# Eggs_Control.net
KiCad netlist of a schematic drawn in EAGLE
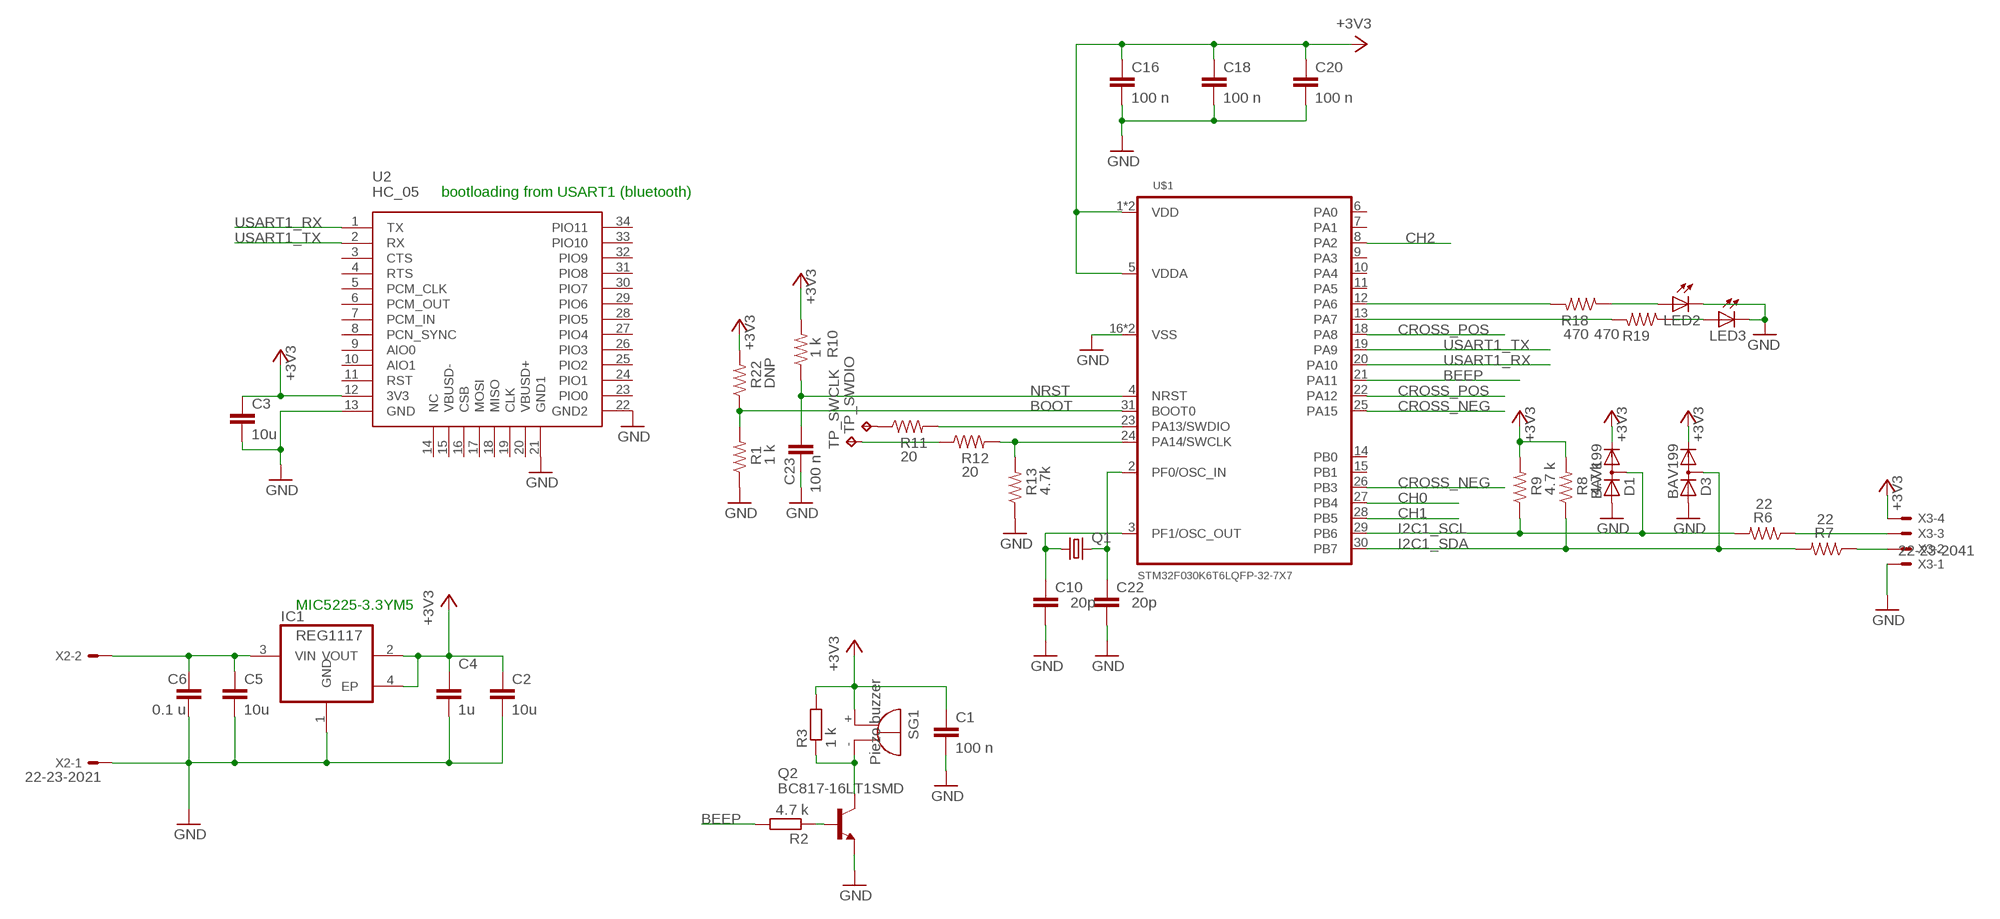
[diagram p0: schematic, sheet 1]
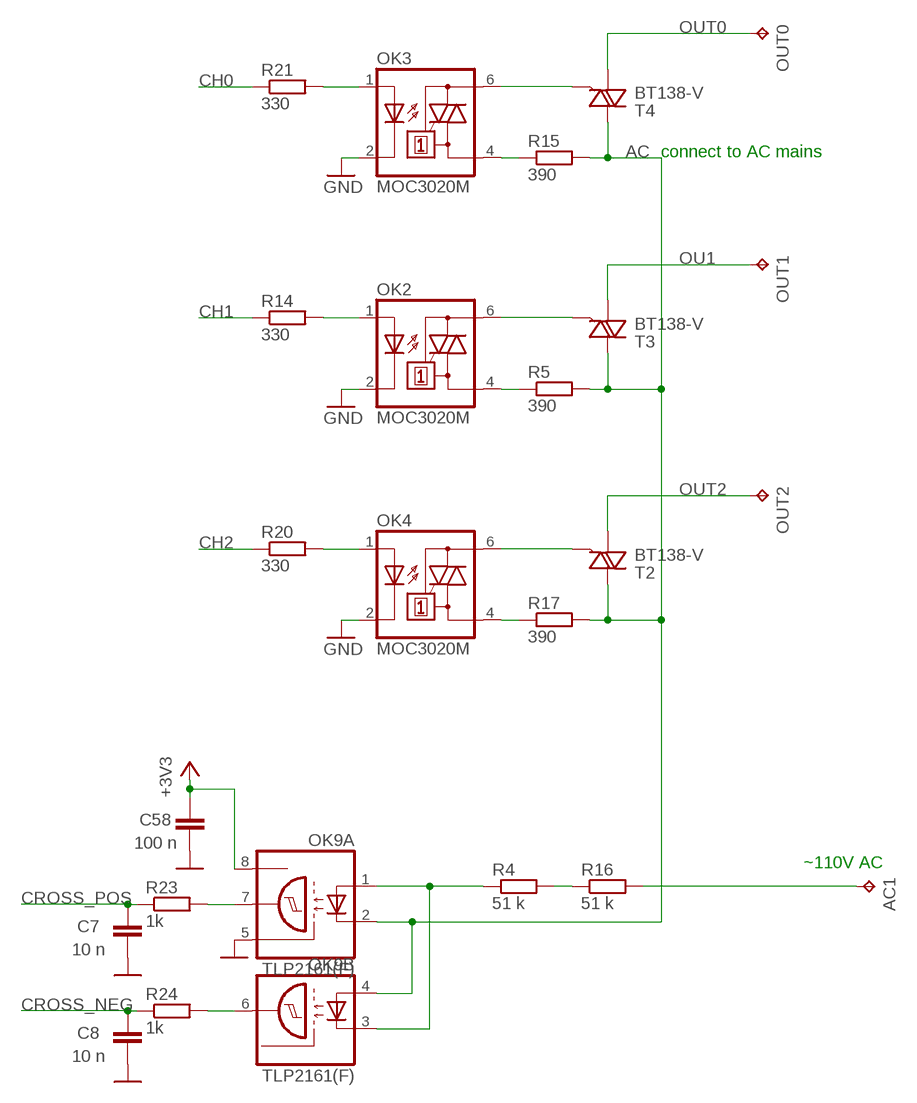
[diagram p1: schematic, sheet 2]

(export (version "E")
  (design (tool "Eeschema 10.0.6"))
  (components
    (comp (ref "C1")
      (value "100 n")
      (footprint "eagle-import:C0603")
      (libsource (lib "eagle-import") (part "C-EUC0603"))
    )
    (comp (ref "C2")
      (value "10u")
      (footprint "eagle-import:C0805")
      (libsource (lib "eagle-import") (part "C-EUC0805"))
    )
    (comp (ref "C3")
      (value "10u")
      (footprint "eagle-import:C0805")
      (libsource (lib "eagle-import") (part "C-EUC0805"))
    )
    (comp (ref "C4")
      (value "1u")
      (footprint "eagle-import:C0603")
      (libsource (lib "eagle-import") (part "C-EUC0603"))
    )
    (comp (ref "C5")
      (value "10u")
      (footprint "eagle-import:C0805")
      (libsource (lib "eagle-import") (part "C-EUC0805"))
    )
    (comp (ref "C6")
      (value "0.1 u")
      (footprint "eagle-import:C0603")
      (libsource (lib "eagle-import") (part "C-EUC0603"))
    )
    (comp (ref "C10")
      (value "20p")
      (footprint "eagle-import:C0603")
      (libsource (lib "eagle-import") (part "C-EUC0603"))
    )
    (comp (ref "C16")
      (value "100 n")
      (footprint "eagle-import:C0603")
      (libsource (lib "eagle-import") (part "C-EUC0603"))
    )
    (comp (ref "C18")
      (value "100 n")
      (footprint "eagle-import:C0603")
      (libsource (lib "eagle-import") (part "C-EUC0603"))
    )
    (comp (ref "C20")
      (value "100 n")
      (footprint "eagle-import:C0603")
      (libsource (lib "eagle-import") (part "C-EUC0603"))
    )
    (comp (ref "C22")
      (value "20p")
      (footprint "eagle-import:C0603")
      (libsource (lib "eagle-import") (part "C-EUC0603"))
    )
    (comp (ref "C23")
      (value "100 n")
      (footprint "eagle-import:C0603")
      (libsource (lib "eagle-import") (part "C-EUC0603"))
    )
    (comp (ref "D1")
      (value "BAV199")
      (footprint "eagle-import:SOT23")
      (libsource (lib "eagle-import") (part "BAV199"))
    )
    (comp (ref "D3")
      (value "BAV199")
      (footprint "eagle-import:SOT23")
      (libsource (lib "eagle-import") (part "BAV199"))
    )
    (comp (ref "IC1")
      (value "REG1117")
      (footprint "eagle-import:SOT223")
      (libsource (lib "eagle-import") (part "REG1117"))
    )
    (comp (ref "LED2")
      (value "LED_ESML0603")
      (footprint "eagle-import:LED_SML0603")
      (libsource (lib "eagle-import") (part "LED_ESML0603"))
    )
    (comp (ref "LED3")
      (value "LED_ESML0603")
      (footprint "eagle-import:LED_SML0603")
      (libsource (lib "eagle-import") (part "LED_ESML0603"))
    )
    (comp (ref "Q1")
      (value "CRYSTALSM49")
      (footprint "eagle-import:SM49")
      (libsource (lib "eagle-import") (part "CRYSTALSM49"))
    )
    (comp (ref "Q2")
      (value "BC817-16LT1SMD")
      (footprint "eagle-import:SOT23-BEC")
      (libsource (lib "eagle-import") (part "BC817SMD-16LT1"))
    )
    (comp (ref "R1")
      (value "1 k")
      (footprint "eagle-import:R0603")
      (libsource (lib "eagle-import") (part "R-US_R0603"))
    )
    (comp (ref "R2")
      (value "4.7 k")
      (footprint "eagle-import:R0603")
      (libsource (lib "eagle-import") (part "resistor_R-EU_R0603"))
    )
    (comp (ref "R3")
      (value "1 k")
      (footprint "eagle-import:R0603")
      (libsource (lib "eagle-import") (part "resistor_R-EU_R0603"))
    )
    (comp (ref "R6")
      (value "22")
      (footprint "eagle-import:R0603")
      (libsource (lib "eagle-import") (part "R-US_R0603"))
    )
    (comp (ref "R7")
      (value "22")
      (footprint "eagle-import:R0603")
      (libsource (lib "eagle-import") (part "R-US_R0603"))
    )
    (comp (ref "R8")
      (value "4.7 k")
      (footprint "eagle-import:R0603")
      (libsource (lib "eagle-import") (part "R-US_R0603"))
    )
    (comp (ref "R9")
      (value "4.7 k")
      (footprint "eagle-import:R0603")
      (libsource (lib "eagle-import") (part "R-US_R0603"))
    )
    (comp (ref "R10")
      (value "1 k")
      (footprint "eagle-import:R0603")
      (libsource (lib "eagle-import") (part "R-US_R0603"))
    )
    (comp (ref "R11")
      (value "20")
      (footprint "eagle-import:R0603")
      (libsource (lib "eagle-import") (part "R-US_R0603"))
    )
    (comp (ref "R12")
      (value "20")
      (footprint "eagle-import:R0603")
      (libsource (lib "eagle-import") (part "R-US_R0603"))
    )
    (comp (ref "R13")
      (value "4.7k")
      (footprint "eagle-import:R0603")
      (libsource (lib "eagle-import") (part "R-US_R0603"))
    )
    (comp (ref "R18")
      (value "470")
      (footprint "eagle-import:R0603")
      (libsource (lib "eagle-import") (part "R-US_R0603"))
    )
    (comp (ref "R19")
      (value "470")
      (footprint "eagle-import:R0603")
      (libsource (lib "eagle-import") (part "R-US_R0603"))
    )
    (comp (ref "R22")
      (value "DNP")
      (footprint "eagle-import:R0603")
      (libsource (lib "eagle-import") (part "R-US_R0603"))
    )
    (comp (ref "SG1")
      (value "Piezo buzzer")
      (footprint "eagle-import:F_HMB")
      (libsource (lib "eagle-import") (part "F/HMB"))
    )
    (comp (ref "TP_SWCLK")
      (value "TPTP10SQ")
      (footprint "eagle-import:TP10SQ")
      (libsource (lib "eagle-import") (part "TPTP10SQ"))
    )
    (comp (ref "TP_SWDIO")
      (value "TPTP10SQ")
      (footprint "eagle-import:TP10SQ")
      (libsource (lib "eagle-import") (part "TPTP10SQ"))
    )
    (comp (ref "U$1")
      (value "STM32F030K6T6LQFP-32-7X7")
      (footprint "eagle-import:LQFP32-7X7")
      (libsource (lib "eagle-import") (part "STM32F030K6T6LQFP-32-7X7"))
    )
    (comp (ref "U2")
      (value "HC_05")
      (footprint "eagle-import:BLUETOOTH_SMD")
      (libsource (lib "eagle-import") (part "HC_05"))
    )
    (comp (ref "X2")
      (value "22-23-2021")
      (footprint "eagle-import:22-23-2021")
      (fields (field (name "MF") "MOLEX"))
      (libsource (lib "eagle-import") (part "22-23-2021"))
    )
    (comp (ref "X3")
      (value "22-23-2041")
      (footprint "eagle-import:22-23-2041")
      (fields (field (name "MF") "MOLEX"))
      (libsource (lib "eagle-import") (part "22-23-2041"))
    )
    (comp (ref "AC1")
      (value "TPPAD1-17")
      (footprint "eagle-import:P1-17")
      (libsource (lib "eagle-import") (part "TPPAD1-17"))
    )
    (comp (ref "C7")
      (value "10 n")
      (footprint "eagle-import:C0603")
      (libsource (lib "eagle-import") (part "C-EUC0603"))
    )
    (comp (ref "C8")
      (value "10 n")
      (footprint "eagle-import:C0603")
      (libsource (lib "eagle-import") (part "C-EUC0603"))
    )
    (comp (ref "C58")
      (value "100 n")
      (footprint "eagle-import:C0603")
      (libsource (lib "eagle-import") (part "C-EUC0603"))
    )
    (comp (ref "OK2")
      (value "MOC3020M")
      (footprint "eagle-import:DIL06")
      (fields (field (name "MF") "FAIRCHILD SEMICONDUCTOR") (field (name "MPN") "MOC3020-M"))
      (libsource (lib "eagle-import") (part "MOC30M20"))
    )
    (comp (ref "OK3")
      (value "MOC3020M")
      (footprint "eagle-import:DIL06")
      (fields (field (name "MF") "FAIRCHILD SEMICONDUCTOR") (field (name "MPN") "MOC3020-M"))
      (libsource (lib "eagle-import") (part "MOC30M20"))
    )
    (comp (ref "OK4")
      (value "MOC3020M")
      (footprint "eagle-import:DIL06")
      (fields (field (name "MF") "FAIRCHILD SEMICONDUCTOR") (field (name "MPN") "MOC3020-M"))
      (libsource (lib "eagle-import") (part "MOC30M20"))
    )
    (comp (ref "OK9")
      (value "TLP2161(F)")
      (footprint "eagle-import:SOIC08-FAIRCHILD")
      (libsource (lib "eagle-import") (part "TLP2161(F)"))
    )
    (comp (ref "OUT0")
      (value "TPPAD1-17")
      (footprint "eagle-import:P1-17")
      (libsource (lib "eagle-import") (part "TPPAD1-17"))
    )
    (comp (ref "OUT1")
      (value "TPPAD1-17")
      (footprint "eagle-import:P1-17")
      (libsource (lib "eagle-import") (part "TPPAD1-17"))
    )
    (comp (ref "OUT2")
      (value "TPPAD1-17")
      (footprint "eagle-import:P1-17")
      (libsource (lib "eagle-import") (part "TPPAD1-17"))
    )
    (comp (ref "R4")
      (value "51 k")
      (footprint "eagle-import:R1206")
      (libsource (lib "eagle-import") (part "resistor_R-EU_R1206"))
    )
    (comp (ref "R5")
      (value "390")
      (footprint "eagle-import:R0603")
      (libsource (lib "eagle-import") (part "R-EU_R0603"))
    )
    (comp (ref "R14")
      (value "330")
      (footprint "eagle-import:R0603")
      (libsource (lib "eagle-import") (part "R-EU_R0603"))
    )
    (comp (ref "R15")
      (value "390")
      (footprint "eagle-import:R0603")
      (libsource (lib "eagle-import") (part "R-EU_R0603"))
    )
    (comp (ref "R16")
      (value "51 k")
      (footprint "eagle-import:R1206")
      (libsource (lib "eagle-import") (part "resistor_R-EU_R1206"))
    )
    (comp (ref "R17")
      (value "390")
      (footprint "eagle-import:R0603")
      (libsource (lib "eagle-import") (part "R-EU_R0603"))
    )
    (comp (ref "R20")
      (value "330")
      (footprint "eagle-import:R0603")
      (libsource (lib "eagle-import") (part "R-EU_R0603"))
    )
    (comp (ref "R21")
      (value "330")
      (footprint "eagle-import:R0603")
      (libsource (lib "eagle-import") (part "R-EU_R0603"))
    )
    (comp (ref "R23")
      (value "1k")
      (footprint "eagle-import:R0603")
      (libsource (lib "eagle-import") (part "R-EU_R0603"))
    )
    (comp (ref "R24")
      (value "1k")
      (footprint "eagle-import:R0603")
      (libsource (lib "eagle-import") (part "R-EU_R0603"))
    )
    (comp (ref "T2")
      (value "BT138-V")
      (footprint "eagle-import:TO220BV")
      (libsource (lib "eagle-import") (part "BT138-V"))
    )
    (comp (ref "T3")
      (value "BT138-V")
      (footprint "eagle-import:TO220BV")
      (libsource (lib "eagle-import") (part "BT138-V"))
    )
    (comp (ref "T4")
      (value "BT138-V")
      (footprint "eagle-import:TO220BV")
      (libsource (lib "eagle-import") (part "BT138-V"))
    )
  )
  (nets
    (net (code "1") (name "+3V3") (class "Default")
      (node (ref "C1") (pin "1") (pinfunction "1_1") (pintype "passive"))
      (node (ref "C16") (pin "1") (pinfunction "1_1") (pintype "passive"))
      (node (ref "C18") (pin "1") (pinfunction "1_1") (pintype "passive"))
      (node (ref "C2") (pin "1") (pinfunction "1_1") (pintype "passive"))
      (node (ref "C20") (pin "1") (pinfunction "1_1") (pintype "passive"))
      (node (ref "C3") (pin "1") (pinfunction "1_1") (pintype "passive"))
      (node (ref "C4") (pin "1") (pinfunction "1_1") (pintype "passive"))
      (node (ref "C58") (pin "1") (pinfunction "1_1") (pintype "passive"))
      (node (ref "D1") (pin "2") (pinfunction "C_2") (pintype "passive"))
      (node (ref "D3") (pin "2") (pinfunction "C_2") (pintype "passive"))
      (node (ref "IC1") (pin "2") (pinfunction "VOUT_2") (pintype "output"))
      (node (ref "IC1") (pin "4") (pinfunction "EP_4") (pintype "output"))
      (node (ref "OK9") (pin "8") (pinfunction "VCC_8") (pintype "passive"))
      (node (ref "R10") (pin "2") (pinfunction "2_2") (pintype "passive"))
      (node (ref "R22") (pin "2") (pinfunction "2_2") (pintype "passive"))
      (node (ref "R3") (pin "2") (pinfunction "2_2") (pintype "passive"))
      (node (ref "R8") (pin "2") (pinfunction "2_2") (pintype "passive"))
      (node (ref "R9") (pin "2") (pinfunction "2_2") (pintype "passive"))
      (node (ref "SG1") (pin "+") (pinfunction "+_+") (pintype "passive"))
      (node (ref "U$1") (pin "1") (pinfunction "VDD_1") (pintype "bidirectional"))
      (node (ref "U$1") (pin "17") (pinfunction "VDD_17") (pintype "bidirectional"))
      (node (ref "U$1") (pin "5") (pinfunction "VDDA_5") (pintype "bidirectional"))
      (node (ref "U2") (pin "12") (pinfunction "3V3_12") (pintype "bidirectional"))
      (node (ref "X3") (pin "4") (pinfunction "S_4") (pintype "passive"))
    )
    (net (code "2") (name "AC") (class "Default")
      (node (ref "OK9") (pin "2") (pinfunction "C_2") (pintype "passive"))
      (node (ref "OK9") (pin "4") (pinfunction "A_4") (pintype "passive"))
      (node (ref "R15") (pin "2") (pinfunction "2_2") (pintype "passive"))
      (node (ref "R17") (pin "2") (pinfunction "2_2") (pintype "passive"))
      (node (ref "R5") (pin "2") (pinfunction "2_2") (pintype "passive"))
      (node (ref "T2") (pin "T2") (pinfunction "A2_T2") (pintype "passive"))
      (node (ref "T3") (pin "T2") (pinfunction "A2_T2") (pintype "passive"))
      (node (ref "T4") (pin "T2") (pinfunction "A2_T2") (pintype "passive"))
    )
    (net (code "3") (name "BEEP") (class "Default")
      (node (ref "R2") (pin "2") (pinfunction "2_2") (pintype "passive"))
      (node (ref "U$1") (pin "21") (pinfunction "PA11_21") (pintype "bidirectional"))
    )
    (net (code "4") (name "BOOT") (class "Default")
      (node (ref "R1") (pin "2") (pinfunction "2_2") (pintype "passive"))
      (node (ref "R22") (pin "1") (pinfunction "1_1") (pintype "passive"))
      (node (ref "U$1") (pin "31") (pinfunction "BOOT0_31") (pintype "bidirectional"))
    )
    (net (code "5") (name "CH0") (class "Default")
      (node (ref "R21") (pin "1") (pinfunction "1_1") (pintype "passive"))
      (node (ref "U$1") (pin "27") (pinfunction "PB4_27") (pintype "bidirectional"))
    )
    (net (code "6") (name "CH1") (class "Default")
      (node (ref "R14") (pin "1") (pinfunction "1_1") (pintype "passive"))
      (node (ref "U$1") (pin "28") (pinfunction "PB5_28") (pintype "bidirectional"))
    )
    (net (code "7") (name "CH2") (class "Default")
      (node (ref "R20") (pin "1") (pinfunction "1_1") (pintype "passive"))
      (node (ref "U$1") (pin "8") (pinfunction "PA2_8") (pintype "bidirectional"))
    )
    (net (code "8") (name "CROSS_NEG") (class "Default")
      (node (ref "C8") (pin "1") (pinfunction "1_1") (pintype "passive"))
      (node (ref "R24") (pin "1") (pinfunction "1_1") (pintype "passive"))
      (node (ref "U$1") (pin "25") (pinfunction "PA15_25") (pintype "bidirectional"))
      (node (ref "U$1") (pin "26") (pinfunction "PB3_26") (pintype "bidirectional"))
    )
    (net (code "9") (name "CROSS_POS") (class "Default")
      (node (ref "C7") (pin "1") (pinfunction "1_1") (pintype "passive"))
      (node (ref "R23") (pin "1") (pinfunction "1_1") (pintype "passive"))
      (node (ref "U$1") (pin "18") (pinfunction "PA8_18") (pintype "bidirectional"))
      (node (ref "U$1") (pin "22") (pinfunction "PA12_22") (pintype "bidirectional"))
    )
    (net (code "10") (name "GND") (class "Default")
      (node (ref "C1") (pin "2") (pinfunction "2_2") (pintype "passive"))
      (node (ref "C10") (pin "2") (pinfunction "2_2") (pintype "passive"))
      (node (ref "C16") (pin "2") (pinfunction "2_2") (pintype "passive"))
      (node (ref "C18") (pin "2") (pinfunction "2_2") (pintype "passive"))
      (node (ref "C2") (pin "2") (pinfunction "2_2") (pintype "passive"))
      (node (ref "C20") (pin "2") (pinfunction "2_2") (pintype "passive"))
      (node (ref "C22") (pin "2") (pinfunction "2_2") (pintype "passive"))
      (node (ref "C23") (pin "2") (pinfunction "2_2") (pintype "passive"))
      (node (ref "C3") (pin "2") (pinfunction "2_2") (pintype "passive"))
      (node (ref "C4") (pin "2") (pinfunction "2_2") (pintype "passive"))
      (node (ref "C5") (pin "2") (pinfunction "2_2") (pintype "passive"))
      (node (ref "C58") (pin "2") (pinfunction "2_2") (pintype "passive"))
      (node (ref "C6") (pin "2") (pinfunction "2_2") (pintype "passive"))
      (node (ref "C7") (pin "2") (pinfunction "2_2") (pintype "passive"))
      (node (ref "C8") (pin "2") (pinfunction "2_2") (pintype "passive"))
      (node (ref "D1") (pin "1") (pinfunction "A_1") (pintype "passive"))
      (node (ref "D3") (pin "1") (pinfunction "A_1") (pintype "passive"))
      (node (ref "IC1") (pin "1") (pinfunction "GND_1") (pintype "power_in"))
      (node (ref "LED2") (pin "C") (pinfunction "C_C") (pintype "passive"))
      (node (ref "LED3") (pin "C") (pinfunction "C_C") (pintype "passive"))
      (node (ref "OK2") (pin "2") (pinfunction "C_2") (pintype "passive"))
      (node (ref "OK3") (pin "2") (pinfunction "C_2") (pintype "passive"))
      (node (ref "OK4") (pin "2") (pinfunction "C_2") (pintype "passive"))
      (node (ref "OK9") (pin "5") (pinfunction "GND_5") (pintype "passive"))
      (node (ref "Q2") (pin "E") (pinfunction "E_E") (pintype "passive"))
      (node (ref "R1") (pin "1") (pinfunction "1_1") (pintype "passive"))
      (node (ref "R13") (pin "1") (pinfunction "1_1") (pintype "passive"))
      (node (ref "U$1") (pin "16") (pinfunction "VSS_16") (pintype "bidirectional"))
      (node (ref "U$1") (pin "32") (pinfunction "VSS_32") (pintype "bidirectional"))
      (node (ref "U2") (pin "13") (pinfunction "GND_13") (pintype "bidirectional"))
      (node (ref "U2") (pin "21") (pinfunction "GND1_21") (pintype "bidirectional"))
      (node (ref "U2") (pin "22") (pinfunction "GND2_22") (pintype "bidirectional"))
      (node (ref "X2") (pin "1") (pinfunction "S_1") (pintype "passive"))
      (node (ref "X3") (pin "1") (pinfunction "S_1") (pintype "passive"))
    )
    (net (code "11") (name "I2C1_SCL") (class "Default")
      (node (ref "D1") (pin "3") (pinfunction "AC_3") (pintype "passive"))
      (node (ref "R6") (pin "2") (pinfunction "2_2") (pintype "passive"))
      (node (ref "R9") (pin "1") (pinfunction "1_1") (pintype "passive"))
      (node (ref "U$1") (pin "29") (pinfunction "PB6_29") (pintype "bidirectional"))
    )
    (net (code "12") (name "I2C1_SDA") (class "Default")
      (node (ref "D3") (pin "3") (pinfunction "AC_3") (pintype "passive"))
      (node (ref "R7") (pin "2") (pinfunction "2_2") (pintype "passive"))
      (node (ref "R8") (pin "1") (pinfunction "1_1") (pintype "passive"))
      (node (ref "U$1") (pin "30") (pinfunction "PB7_30") (pintype "bidirectional"))
    )
    (net (code "13") (name "NRST") (class "Default")
      (node (ref "C23") (pin "1") (pinfunction "1_1") (pintype "passive"))
      (node (ref "R10") (pin "1") (pinfunction "1_1") (pintype "passive"))
      (node (ref "U$1") (pin "4") (pinfunction "NRST_4") (pintype "bidirectional"))
    )
    (net (code "14") (name "Net-(AC1-PadTP)") (class "Default")
      (node (ref "AC1") (pin "TP") (pinfunction "TP_TP") (pintype "input"))
      (node (ref "R16") (pin "2") (pinfunction "2_2") (pintype "passive"))
    )
    (net (code "15") (name "Net-(IC1-VIN)") (class "Default")
      (node (ref "C5") (pin "1") (pinfunction "1_1") (pintype "passive"))
      (node (ref "C6") (pin "1") (pinfunction "1_1") (pintype "passive"))
      (node (ref "IC1") (pin "3") (pinfunction "VIN_3") (pintype "input"))
      (node (ref "X2") (pin "2") (pinfunction "S_2") (pintype "passive"))
    )
    (net (code "16") (name "Net-(LED2-PadA)") (class "Default")
      (node (ref "LED2") (pin "A") (pinfunction "A_A") (pintype "passive"))
      (node (ref "R18") (pin "1") (pinfunction "1_1") (pintype "passive"))
    )
    (net (code "17") (name "Net-(LED3-PadA)") (class "Default")
      (node (ref "LED3") (pin "A") (pinfunction "A_A") (pintype "passive"))
      (node (ref "R19") (pin "1") (pinfunction "1_1") (pintype "passive"))
    )
    (net (code "18") (name "Net-(OK2-A)") (class "Default")
      (node (ref "OK2") (pin "1") (pinfunction "A_1") (pintype "passive"))
      (node (ref "R14") (pin "2") (pinfunction "2_2") (pintype "passive"))
    )
    (net (code "19") (name "Net-(OK2-A1)") (class "Default")
      (node (ref "OK2") (pin "4") (pinfunction "A1_4") (pintype "passive"))
      (node (ref "R5") (pin "1") (pinfunction "1_1") (pintype "passive"))
    )
    (net (code "20") (name "Net-(OK2-A2)") (class "Default")
      (node (ref "OK2") (pin "6") (pinfunction "A2_6") (pintype "passive"))
      (node (ref "T3") (pin "G") (pinfunction "G_G") (pintype "passive"))
    )
    (net (code "21") (name "Net-(OK3-A)") (class "Default")
      (node (ref "OK3") (pin "1") (pinfunction "A_1") (pintype "passive"))
      (node (ref "R21") (pin "2") (pinfunction "2_2") (pintype "passive"))
    )
    (net (code "22") (name "Net-(OK3-A1)") (class "Default")
      (node (ref "OK3") (pin "4") (pinfunction "A1_4") (pintype "passive"))
      (node (ref "R15") (pin "1") (pinfunction "1_1") (pintype "passive"))
    )
    (net (code "23") (name "Net-(OK3-A2)") (class "Default")
      (node (ref "OK3") (pin "6") (pinfunction "A2_6") (pintype "passive"))
      (node (ref "T4") (pin "G") (pinfunction "G_G") (pintype "passive"))
    )
    (net (code "24") (name "Net-(OK4-A)") (class "Default")
      (node (ref "OK4") (pin "1") (pinfunction "A_1") (pintype "passive"))
      (node (ref "R20") (pin "2") (pinfunction "2_2") (pintype "passive"))
    )
    (net (code "25") (name "Net-(OK4-A1)") (class "Default")
      (node (ref "OK4") (pin "4") (pinfunction "A1_4") (pintype "passive"))
      (node (ref "R17") (pin "1") (pinfunction "1_1") (pintype "passive"))
    )
    (net (code "26") (name "Net-(OK4-A2)") (class "Default")
      (node (ref "OK4") (pin "6") (pinfunction "A2_6") (pintype "passive"))
      (node (ref "T2") (pin "G") (pinfunction "G_G") (pintype "passive"))
    )
    (net (code "27") (name "Net-(OK9A-A)") (class "Default")
      (node (ref "OK9") (pin "1") (pinfunction "A_1") (pintype "passive"))
      (node (ref "OK9") (pin "3") (pinfunction "C_3") (pintype "passive"))
      (node (ref "R4") (pin "1") (pinfunction "1_1") (pintype "passive"))
    )
    (net (code "28") (name "Net-(OK9A-OUT)") (class "Default")
      (node (ref "OK9") (pin "7") (pinfunction "OUT_7") (pintype "passive"))
      (node (ref "R23") (pin "2") (pinfunction "2_2") (pintype "passive"))
    )
    (net (code "29") (name "Net-(OK9B-OUT)") (class "Default")
      (node (ref "OK9") (pin "6") (pinfunction "OUT_6") (pintype "passive"))
      (node (ref "R24") (pin "2") (pinfunction "2_2") (pintype "passive"))
    )
    (net (code "30") (name "Net-(Q2-PadB)") (class "Default")
      (node (ref "Q2") (pin "B") (pinfunction "B_B") (pintype "passive"))
      (node (ref "R2") (pin "1") (pinfunction "1_1") (pintype "passive"))
    )
    (net (code "31") (name "Net-(Q2-PadC)") (class "Default")
      (node (ref "Q2") (pin "C") (pinfunction "C_C") (pintype "passive"))
      (node (ref "R3") (pin "1") (pinfunction "1_1") (pintype "passive"))
      (node (ref "SG1") (pin "-") (pinfunction "-_-") (pintype "passive"))
    )
    (net (code "32") (name "Net-(R11-Pad1)") (class "Default")
      (node (ref "R11") (pin "1") (pinfunction "1_1") (pintype "passive"))
      (node (ref "TP_SWDIO") (pin "TP") (pinfunction "TP_TP") (pintype "input"))
    )
    (net (code "33") (name "Net-(R12-Pad1)") (class "Default")
      (node (ref "R12") (pin "1") (pinfunction "1_1") (pintype "passive"))
      (node (ref "TP_SWCLK") (pin "TP") (pinfunction "TP_TP") (pintype "input"))
    )
    (net (code "34") (name "Net-(R16-Pad1)") (class "Default")
      (node (ref "R16") (pin "1") (pinfunction "1_1") (pintype "passive"))
      (node (ref "R4") (pin "2") (pinfunction "2_2") (pintype "passive"))
    )
    (net (code "35") (name "Net-(U$1-PA6)") (class "Default")
      (node (ref "R18") (pin "2") (pinfunction "2_2") (pintype "passive"))
      (node (ref "U$1") (pin "12") (pinfunction "PA6_12") (pintype "bidirectional"))
    )
    (net (code "36") (name "Net-(U$1-PA7)") (class "Default")
      (node (ref "R19") (pin "2") (pinfunction "2_2") (pintype "passive"))
      (node (ref "U$1") (pin "13") (pinfunction "PA7_13") (pintype "bidirectional"))
    )
    (net (code "37") (name "Net-(U$1-PA13{slash}SWDIO)") (class "Default")
      (node (ref "R11") (pin "2") (pinfunction "2_2") (pintype "passive"))
      (node (ref "U$1") (pin "23") (pinfunction "PA13/SWDIO_23") (pintype "bidirectional"))
    )
    (net (code "38") (name "Net-(U$1-PA14{slash}SWCLK)") (class "Default")
      (node (ref "R12") (pin "2") (pinfunction "2_2") (pintype "passive"))
      (node (ref "R13") (pin "2") (pinfunction "2_2") (pintype "passive"))
      (node (ref "U$1") (pin "24") (pinfunction "PA14/SWCLK_24") (pintype "bidirectional"))
    )
    (net (code "39") (name "Net-(U$1-PF0{slash}OSC_IN)") (class "Default")
      (node (ref "C22") (pin "1") (pinfunction "1_1") (pintype "passive"))
      (node (ref "Q1") (pin "2") (pinfunction "2_2") (pintype "passive"))
      (node (ref "U$1") (pin "2") (pinfunction "PF0/OSC_IN_2") (pintype "bidirectional"))
    )
    (net (code "40") (name "Net-(U$1-PF1{slash}OSC_OUT)") (class "Default")
      (node (ref "C10") (pin "1") (pinfunction "1_1") (pintype "passive"))
      (node (ref "Q1") (pin "1") (pinfunction "1_1") (pintype "passive"))
      (node (ref "U$1") (pin "3") (pinfunction "PF1/OSC_OUT_3") (pintype "bidirectional"))
    )
    (net (code "41") (name "Net-(X3B-S)") (class "Default")
      (node (ref "R7") (pin "1") (pinfunction "1_1") (pintype "passive"))
      (node (ref "X3") (pin "2") (pinfunction "S_2") (pintype "passive"))
    )
    (net (code "42") (name "Net-(X3C-S)") (class "Default")
      (node (ref "R6") (pin "1") (pinfunction "1_1") (pintype "passive"))
      (node (ref "X3") (pin "3") (pinfunction "S_3") (pintype "passive"))
    )
    (net (code "43") (name "OU1") (class "Default")
      (node (ref "OUT1") (pin "TP") (pinfunction "TP_TP") (pintype "input"))
      (node (ref "T3") (pin "T1") (pinfunction "A1_T1") (pintype "passive"))
    )
    (net (code "44") (name "OUT0") (class "Default")
      (node (ref "OUT0") (pin "TP") (pinfunction "TP_TP") (pintype "input"))
      (node (ref "T4") (pin "T1") (pinfunction "A1_T1") (pintype "passive"))
    )
    (net (code "45") (name "OUT2") (class "Default")
      (node (ref "OUT2") (pin "TP") (pinfunction "TP_TP") (pintype "input"))
      (node (ref "T2") (pin "T1") (pinfunction "A1_T1") (pintype "passive"))
    )
    (net (code "46") (name "USART1_RX") (class "Default")
      (node (ref "U$1") (pin "20") (pinfunction "PA10_20") (pintype "bidirectional"))
      (node (ref "U2") (pin "1") (pinfunction "TX_1") (pintype "bidirectional"))
    )
    (net (code "47") (name "USART1_TX") (class "Default")
      (node (ref "U$1") (pin "19") (pinfunction "PA9_19") (pintype "bidirectional"))
      (node (ref "U2") (pin "2") (pinfunction "RX_2") (pintype "bidirectional"))
    )
    (net (code "48") (name "unconnected-(U$1-PA0-Pad6)") (class "Default")
      (node (ref "U$1") (pin "6") (pinfunction "PA0_6") (pintype "bidirectional"))
    )
    (net (code "49") (name "unconnected-(U$1-PA1-Pad7)") (class "Default")
      (node (ref "U$1") (pin "7") (pinfunction "PA1_7") (pintype "bidirectional"))
    )
    (net (code "50") (name "unconnected-(U$1-PA3-Pad9)") (class "Default")
      (node (ref "U$1") (pin "9") (pinfunction "PA3_9") (pintype "bidirectional"))
    )
    (net (code "51") (name "unconnected-(U$1-PA4-Pad10)") (class "Default")
      (node (ref "U$1") (pin "10") (pinfunction "PA4_10") (pintype "bidirectional"))
    )
    (net (code "52") (name "unconnected-(U$1-PA5-Pad11)") (class "Default")
      (node (ref "U$1") (pin "11") (pinfunction "PA5_11") (pintype "bidirectional"))
    )
    (net (code "53") (name "unconnected-(U$1-PB0-Pad14)") (class "Default")
      (node (ref "U$1") (pin "14") (pinfunction "PB0_14") (pintype "bidirectional"))
    )
    (net (code "54") (name "unconnected-(U$1-PB1-Pad15)") (class "Default")
      (node (ref "U$1") (pin "15") (pinfunction "PB1_15") (pintype "bidirectional"))
    )
    (net (code "55") (name "unconnected-(U2-AIO0-Pad9)") (class "Default")
      (node (ref "U2") (pin "9") (pinfunction "AIO0_9") (pintype "bidirectional"))
    )
    (net (code "56") (name "unconnected-(U2-AIO1-Pad10)") (class "Default")
      (node (ref "U2") (pin "10") (pinfunction "AIO1_10") (pintype "bidirectional"))
    )
    (net (code "57") (name "unconnected-(U2-CLK-Pad19)") (class "Default")
      (node (ref "U2") (pin "19") (pinfunction "CLK_19") (pintype "bidirectional"))
    )
    (net (code "58") (name "unconnected-(U2-CSB-Pad16)") (class "Default")
      (node (ref "U2") (pin "16") (pinfunction "CSB_16") (pintype "bidirectional"))
    )
    (net (code "59") (name "unconnected-(U2-CTS-Pad3)") (class "Default")
      (node (ref "U2") (pin "3") (pinfunction "CTS_3") (pintype "bidirectional"))
    )
    (net (code "60") (name "unconnected-(U2-MISO-Pad18)") (class "Default")
      (node (ref "U2") (pin "18") (pinfunction "MISO_18") (pintype "bidirectional"))
    )
    (net (code "61") (name "unconnected-(U2-MOSI-Pad17)") (class "Default")
      (node (ref "U2") (pin "17") (pinfunction "MOSI_17") (pintype "bidirectional"))
    )
    (net (code "62") (name "unconnected-(U2-NC-Pad14)") (class "Default")
      (node (ref "U2") (pin "14") (pinfunction "NC_14") (pintype "bidirectional"))
    )
    (net (code "63") (name "unconnected-(U2-PCM_CLK-Pad5)") (class "Default")
      (node (ref "U2") (pin "5") (pinfunction "PCM_CLK_5") (pintype "bidirectional"))
    )
    (net (code "64") (name "unconnected-(U2-PCM_IN-Pad7)") (class "Default")
      (node (ref "U2") (pin "7") (pinfunction "PCM_IN_7") (pintype "bidirectional"))
    )
    (net (code "65") (name "unconnected-(U2-PCM_OUT-Pad6)") (class "Default")
      (node (ref "U2") (pin "6") (pinfunction "PCM_OUT_6") (pintype "bidirectional"))
    )
    (net (code "66") (name "unconnected-(U2-PCN_SYNC-Pad8)") (class "Default")
      (node (ref "U2") (pin "8") (pinfunction "PCN_SYNC_8") (pintype "bidirectional"))
    )
    (net (code "67") (name "unconnected-(U2-PIO0-Pad23)") (class "Default")
      (node (ref "U2") (pin "23") (pinfunction "PIO0_23") (pintype "bidirectional"))
    )
    (net (code "68") (name "unconnected-(U2-PIO1-Pad24)") (class "Default")
      (node (ref "U2") (pin "24") (pinfunction "PIO1_24") (pintype "bidirectional"))
    )
    (net (code "69") (name "unconnected-(U2-PIO2-Pad25)") (class "Default")
      (node (ref "U2") (pin "25") (pinfunction "PIO2_25") (pintype "bidirectional"))
    )
    (net (code "70") (name "unconnected-(U2-PIO3-Pad26)") (class "Default")
      (node (ref "U2") (pin "26") (pinfunction "PIO3_26") (pintype "bidirectional"))
    )
    (net (code "71") (name "unconnected-(U2-PIO4-Pad27)") (class "Default")
      (node (ref "U2") (pin "27") (pinfunction "PIO4_27") (pintype "bidirectional"))
    )
    (net (code "72") (name "unconnected-(U2-PIO5-Pad28)") (class "Default")
      (node (ref "U2") (pin "28") (pinfunction "PIO5_28") (pintype "bidirectional"))
    )
    (net (code "73") (name "unconnected-(U2-PIO6-Pad29)") (class "Default")
      (node (ref "U2") (pin "29") (pinfunction "PIO6_29") (pintype "bidirectional"))
    )
    (net (code "74") (name "unconnected-(U2-PIO7-Pad30)") (class "Default")
      (node (ref "U2") (pin "30") (pinfunction "PIO7_30") (pintype "bidirectional"))
    )
    (net (code "75") (name "unconnected-(U2-PIO8-Pad31)") (class "Default")
      (node (ref "U2") (pin "31") (pinfunction "PIO8_31") (pintype "bidirectional"))
    )
    (net (code "76") (name "unconnected-(U2-PIO9-Pad32)") (class "Default")
      (node (ref "U2") (pin "32") (pinfunction "PIO9_32") (pintype "bidirectional"))
    )
    (net (code "77") (name "unconnected-(U2-PIO10-Pad33)") (class "Default")
      (node (ref "U2") (pin "33") (pinfunction "PIO10_33") (pintype "bidirectional"))
    )
    (net (code "78") (name "unconnected-(U2-PIO11-Pad34)") (class "Default")
      (node (ref "U2") (pin "34") (pinfunction "PIO11_34") (pintype "bidirectional"))
    )
    (net (code "79") (name "unconnected-(U2-RST-Pad11)") (class "Default")
      (node (ref "U2") (pin "11") (pinfunction "RST_11") (pintype "bidirectional"))
    )
    (net (code "80") (name "unconnected-(U2-RTS-Pad4)") (class "Default")
      (node (ref "U2") (pin "4") (pinfunction "RTS_4") (pintype "bidirectional"))
    )
    (net (code "81") (name "unconnected-(U2-VBUSD+-Pad20)") (class "Default")
      (node (ref "U2") (pin "20") (pinfunction "VBUSD+_20") (pintype "bidirectional"))
    )
    (net (code "82") (name "unconnected-(U2-VBUSD--Pad15)") (class "Default")
      (node (ref "U2") (pin "15") (pinfunction "VBUSD-_15") (pintype "bidirectional"))
    )
  )
)
